# bucket.net
KiCad netlist of a schematic drawn in EAGLE
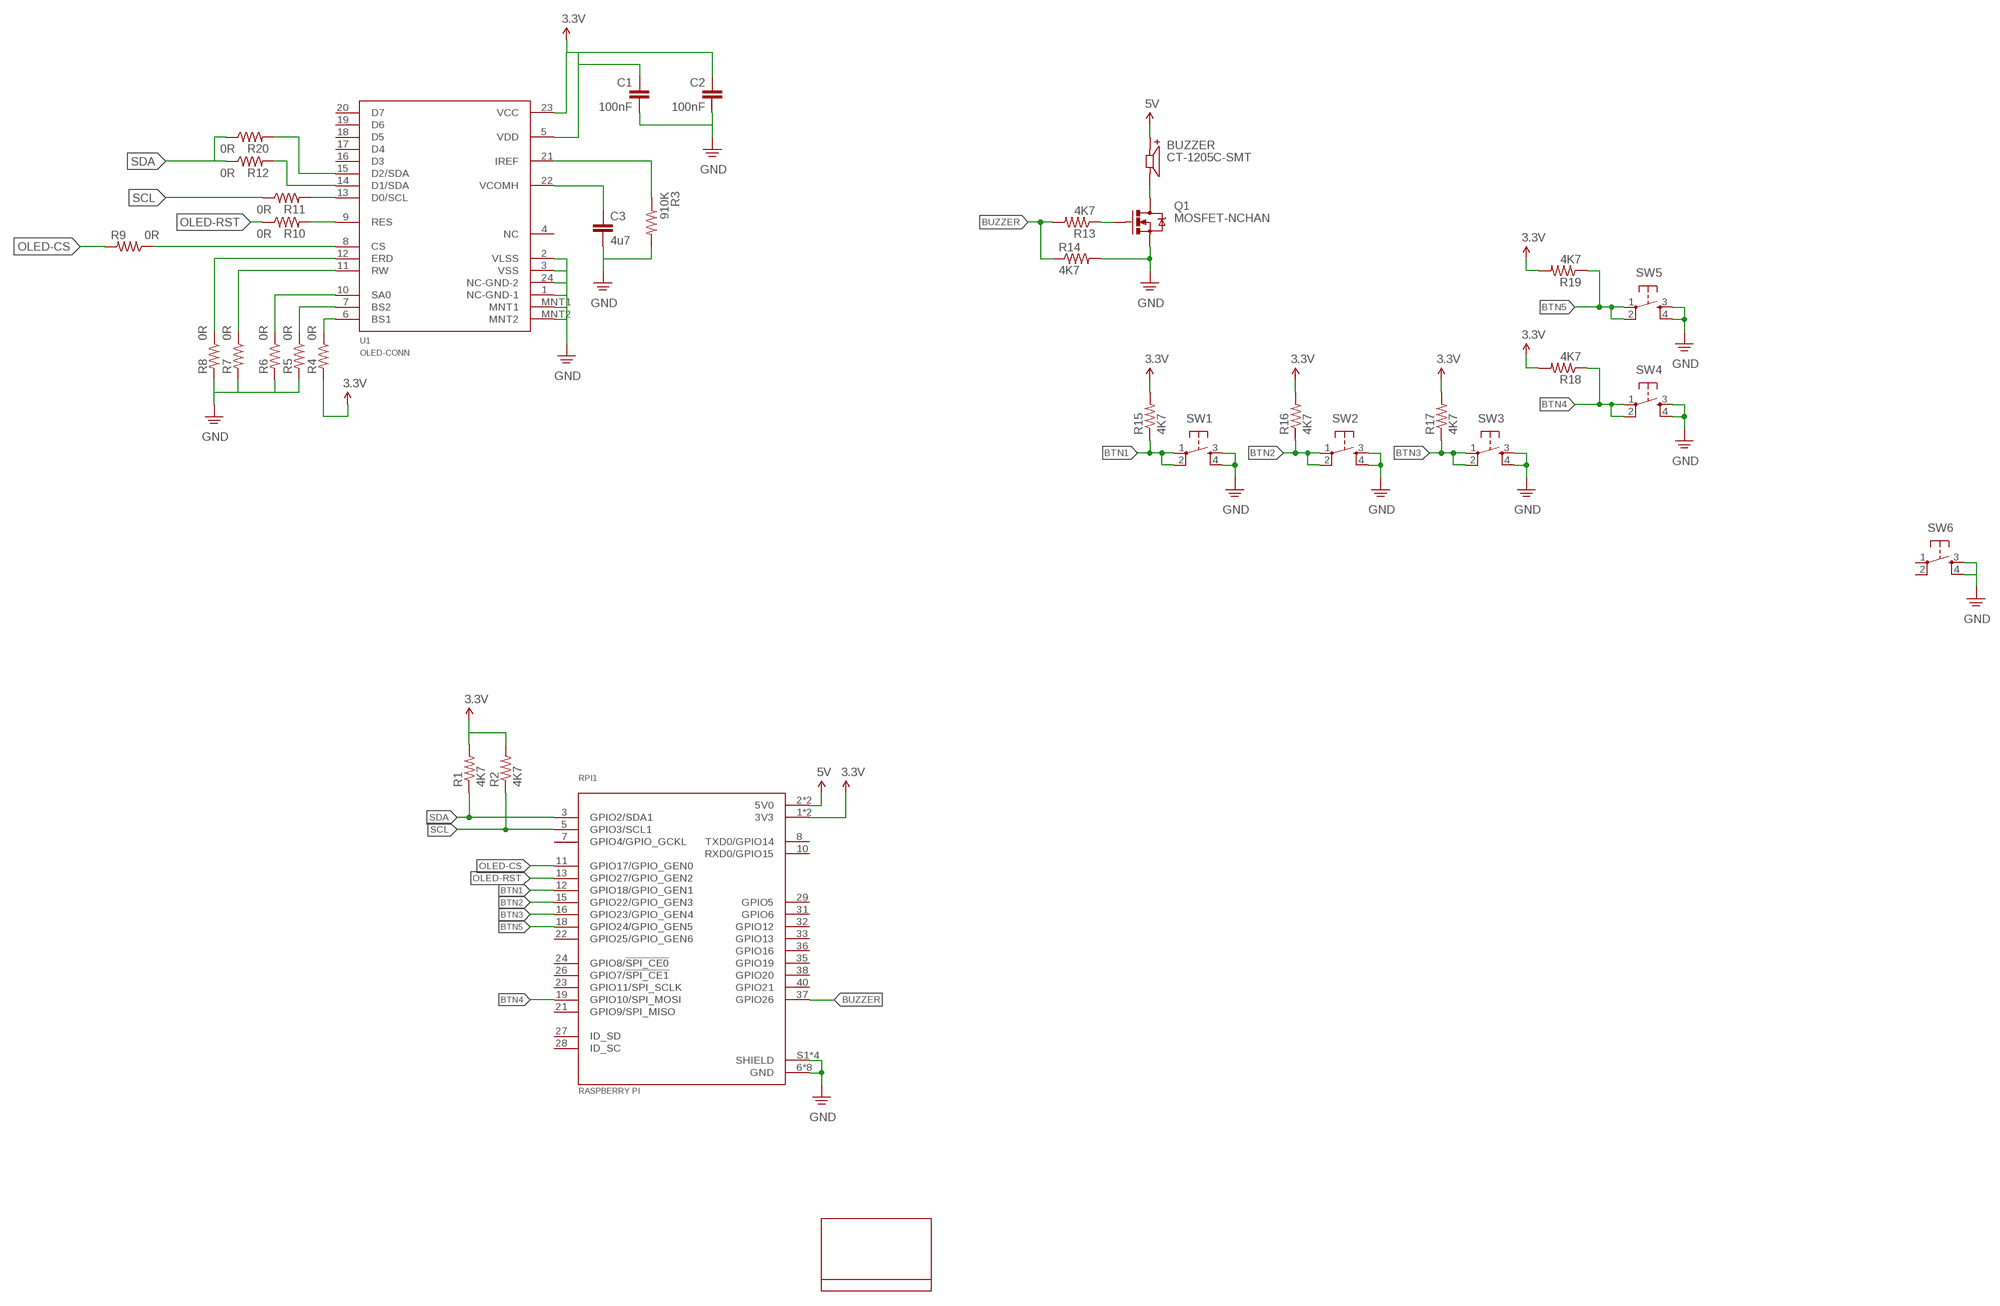
[diagram p0: schematic, sheet 1]

(export (version "E")
  (design (tool "Eeschema 10.0.6"))
  (components
    (comp (ref "BUZZER")
      (value "CT-1205C-SMT")
      (footprint "eagle-import:CUI_CT-1205C-SMT")
      (fields (field (name "MF") "CUI DEVICES"))
      (libsource (lib "eagle-import") (part "CT-1205C-SMT"))
    )
    (comp (ref "C1")
      (value "100nF")
      (footprint "eagle-import:0603-CAP")
      (libsource (lib "eagle-import") (part "CAP0603-CAP"))
    )
    (comp (ref "C2")
      (value "100nF")
      (footprint "eagle-import:0603-CAP")
      (libsource (lib "eagle-import") (part "CAP0603-CAP"))
    )
    (comp (ref "C3")
      (value "4u7")
      (footprint "eagle-import:0603-CAP")
      (libsource (lib "eagle-import") (part "CAP0603-CAP"))
    )
    (comp (ref "Q1")
      (value "MOSFET-NCHAN")
      (footprint "eagle-import:SOT23-3")
      (libsource (lib "eagle-import") (part "MOSFET-NCHANNELSMD"))
    )
    (comp (ref "R1")
      (value "4K7")
      (footprint "eagle-import:0603-RES")
      (libsource (lib "eagle-import") (part "RESISTOR0603-RES"))
    )
    (comp (ref "R2")
      (value "4K7")
      (footprint "eagle-import:0603-RES")
      (libsource (lib "eagle-import") (part "RESISTOR0603-RES"))
    )
    (comp (ref "R3")
      (value "910K")
      (footprint "eagle-import:0603-RES")
      (libsource (lib "eagle-import") (part "RESISTOR0603-RES"))
    )
    (comp (ref "R4")
      (value "0R")
      (footprint "eagle-import:0603-RES")
      (libsource (lib "eagle-import") (part "RESISTOR0603-RES"))
    )
    (comp (ref "R5")
      (value "0R")
      (footprint "eagle-import:0603-RES")
      (libsource (lib "eagle-import") (part "RESISTOR0603-RES"))
    )
    (comp (ref "R6")
      (value "0R")
      (footprint "eagle-import:0603-RES")
      (libsource (lib "eagle-import") (part "RESISTOR0603-RES"))
    )
    (comp (ref "R7")
      (value "0R")
      (footprint "eagle-import:0603-RES")
      (libsource (lib "eagle-import") (part "RESISTOR0603-RES"))
    )
    (comp (ref "R8")
      (value "0R")
      (footprint "eagle-import:0603-RES")
      (libsource (lib "eagle-import") (part "RESISTOR0603-RES"))
    )
    (comp (ref "R9")
      (value "0R")
      (footprint "eagle-import:0603-RES")
      (libsource (lib "eagle-import") (part "RESISTOR0603-RES"))
    )
    (comp (ref "R10")
      (value "0R")
      (footprint "eagle-import:0603-RES")
      (libsource (lib "eagle-import") (part "RESISTOR0603-RES"))
    )
    (comp (ref "R11")
      (value "0R")
      (footprint "eagle-import:0603-RES")
      (libsource (lib "eagle-import") (part "RESISTOR0603-RES"))
    )
    (comp (ref "R12")
      (value "0R")
      (footprint "eagle-import:0603-RES")
      (libsource (lib "eagle-import") (part "RESISTOR0603-RES"))
    )
    (comp (ref "R13")
      (value "4K7")
      (footprint "eagle-import:0603-RES")
      (libsource (lib "eagle-import") (part "RESISTOR0603-RES"))
    )
    (comp (ref "R14")
      (value "4K7")
      (footprint "eagle-import:0603-RES")
      (libsource (lib "eagle-import") (part "RESISTOR0603-RES"))
    )
    (comp (ref "R15")
      (value "4K7")
      (footprint "eagle-import:0603-RES")
      (libsource (lib "eagle-import") (part "RESISTOR0603-RES"))
    )
    (comp (ref "R16")
      (value "4K7")
      (footprint "eagle-import:0603-RES")
      (libsource (lib "eagle-import") (part "RESISTOR0603-RES"))
    )
    (comp (ref "R17")
      (value "4K7")
      (footprint "eagle-import:0603-RES")
      (libsource (lib "eagle-import") (part "RESISTOR0603-RES"))
    )
    (comp (ref "R18")
      (value "4K7")
      (footprint "eagle-import:0603-RES")
      (libsource (lib "eagle-import") (part "RESISTOR0603-RES"))
    )
    (comp (ref "R19")
      (value "4K7")
      (footprint "eagle-import:0603-RES")
      (libsource (lib "eagle-import") (part "RESISTOR0603-RES"))
    )
    (comp (ref "R20")
      (value "0R")
      (footprint "eagle-import:0603-RES")
      (libsource (lib "eagle-import") (part "RESISTOR0603-RES"))
    )
    (comp (ref "RPI1")
      (value "RASPBERRY PI")
      (footprint "eagle-import:MODULE_RASPBERRY_PI_3_MODEL_B+")
      (libsource (lib "eagle-import") (part "RASPBERRY_PI_3_MODEL_B+"))
    )
    (comp (ref "SW1")
      (value "TAC_SWITCHPTH")
      (footprint "eagle-import:TACTILE-PTH")
      (libsource (lib "eagle-import") (part "TAC_SWITCHPTH"))
    )
    (comp (ref "SW2")
      (value "TAC_SWITCHPTH")
      (footprint "eagle-import:TACTILE-PTH")
      (libsource (lib "eagle-import") (part "TAC_SWITCHPTH"))
    )
    (comp (ref "SW3")
      (value "TAC_SWITCHPTH")
      (footprint "eagle-import:TACTILE-PTH")
      (libsource (lib "eagle-import") (part "TAC_SWITCHPTH"))
    )
    (comp (ref "SW4")
      (value "TAC_SWITCHPTH")
      (footprint "eagle-import:TACTILE-PTH")
      (libsource (lib "eagle-import") (part "TAC_SWITCHPTH"))
    )
    (comp (ref "SW5")
      (value "TAC_SWITCHPTH")
      (footprint "eagle-import:TACTILE-PTH")
      (libsource (lib "eagle-import") (part "TAC_SWITCHPTH"))
    )
    (comp (ref "SW6")
      (value "TAC_SWITCHPTH")
      (footprint "eagle-import:TACTILE-PTH")
      (libsource (lib "eagle-import") (part "TAC_SWITCHPTH"))
    )
    (comp (ref "U$1")
      (value "OLED-PANEL-1.54IN")
      (footprint "eagle-import:OLED-1.54IN")
      (libsource (lib "eagle-import") (part "OLED-PANEL-1.54IN"))
    )
    (comp (ref "U1")
      (value "OLED-CONN")
      (footprint "eagle-import:CONN24_1X24_DRC_FFC_HIR")
      (libsource (lib "eagle-import") (part "OLED-CONN"))
    )
  )
  (nets
    (net (code "1") (name "3.3V") (class "Default")
      (node (ref "C1") (pin "1") (pinfunction "1_1") (pintype "passive"))
      (node (ref "C2") (pin "1") (pinfunction "1_1") (pintype "passive"))
      (node (ref "R1") (pin "2") (pinfunction "2_2") (pintype "passive"))
      (node (ref "R15") (pin "2") (pinfunction "2_2") (pintype "passive"))
      (node (ref "R16") (pin "2") (pinfunction "2_2") (pintype "passive"))
      (node (ref "R17") (pin "2") (pinfunction "2_2") (pintype "passive"))
      (node (ref "R18") (pin "2") (pinfunction "2_2") (pintype "passive"))
      (node (ref "R19") (pin "2") (pinfunction "2_2") (pintype "passive"))
      (node (ref "R2") (pin "2") (pinfunction "2_2") (pintype "passive"))
      (node (ref "R4") (pin "2") (pinfunction "2_2") (pintype "passive"))
      (node (ref "RPI1") (pin "1") (pinfunction "3V3_1") (pintype "power_in"))
      (node (ref "RPI1") (pin "17") (pinfunction "3V3_17") (pintype "power_in"))
      (node (ref "U1") (pin "23") (pinfunction "VCC_23") (pintype "input"))
      (node (ref "U1") (pin "5") (pinfunction "VDD_5") (pintype "input"))
    )
    (net (code "2") (name "5V") (class "Default")
      (node (ref "BUZZER") (pin "1") (pinfunction "1_1") (pintype "passive"))
      (node (ref "RPI1") (pin "2") (pinfunction "5V0_2") (pintype "power_in"))
      (node (ref "RPI1") (pin "4") (pinfunction "5V0_4") (pintype "power_in"))
    )
    (net (code "3") (name "BTN1") (class "Default")
      (node (ref "R15") (pin "1") (pinfunction "1_1") (pintype "passive"))
      (node (ref "RPI1") (pin "12") (pinfunction "GPIO18/GPIO_GEN1_12") (pintype "bidirectional"))
      (node (ref "SW1") (pin "1") (pinfunction "1_1") (pintype "passive"))
      (node (ref "SW1") (pin "2") (pinfunction "2_2") (pintype "passive"))
    )
    (net (code "4") (name "BTN2") (class "Default")
      (node (ref "R16") (pin "1") (pinfunction "1_1") (pintype "passive"))
      (node (ref "RPI1") (pin "15") (pinfunction "GPIO22/GPIO_GEN3_15") (pintype "bidirectional"))
      (node (ref "SW2") (pin "1") (pinfunction "1_1") (pintype "passive"))
      (node (ref "SW2") (pin "2") (pinfunction "2_2") (pintype "passive"))
    )
    (net (code "5") (name "BTN3") (class "Default")
      (node (ref "R17") (pin "1") (pinfunction "1_1") (pintype "passive"))
      (node (ref "RPI1") (pin "16") (pinfunction "GPIO23/GPIO_GEN4_16") (pintype "bidirectional"))
      (node (ref "SW3") (pin "1") (pinfunction "1_1") (pintype "passive"))
      (node (ref "SW3") (pin "2") (pinfunction "2_2") (pintype "passive"))
    )
    (net (code "6") (name "BTN4") (class "Default")
      (node (ref "R18") (pin "1") (pinfunction "1_1") (pintype "passive"))
      (node (ref "RPI1") (pin "19") (pinfunction "GPIO10/SPI_MOSI_19") (pintype "bidirectional"))
      (node (ref "SW4") (pin "1") (pinfunction "1_1") (pintype "passive"))
      (node (ref "SW4") (pin "2") (pinfunction "2_2") (pintype "passive"))
    )
    (net (code "7") (name "BTN5") (class "Default")
      (node (ref "R19") (pin "1") (pinfunction "1_1") (pintype "passive"))
      (node (ref "RPI1") (pin "18") (pinfunction "GPIO24/GPIO_GEN5_18") (pintype "bidirectional"))
      (node (ref "SW5") (pin "1") (pinfunction "1_1") (pintype "passive"))
      (node (ref "SW5") (pin "2") (pinfunction "2_2") (pintype "passive"))
    )
    (net (code "8") (name "BUZZER") (class "Default")
      (node (ref "R13") (pin "2") (pinfunction "2_2") (pintype "passive"))
      (node (ref "R14") (pin "1") (pinfunction "1_1") (pintype "passive"))
      (node (ref "RPI1") (pin "37") (pinfunction "GPIO26_37") (pintype "bidirectional"))
    )
    (net (code "9") (name "GND") (class "Default")
      (node (ref "C1") (pin "2") (pinfunction "2_2") (pintype "passive"))
      (node (ref "C2") (pin "2") (pinfunction "2_2") (pintype "passive"))
      (node (ref "C3") (pin "2") (pinfunction "2_2") (pintype "passive"))
      (node (ref "Q1") (pin "2") (pinfunction "S_2") (pintype "passive"))
      (node (ref "R14") (pin "2") (pinfunction "2_2") (pintype "passive"))
      (node (ref "R3") (pin "2") (pinfunction "2_2") (pintype "passive"))
      (node (ref "R5") (pin "2") (pinfunction "2_2") (pintype "passive"))
      (node (ref "R6") (pin "2") (pinfunction "2_2") (pintype "passive"))
      (node (ref "R7") (pin "2") (pinfunction "2_2") (pintype "passive"))
      (node (ref "R8") (pin "2") (pinfunction "2_2") (pintype "passive"))
      (node (ref "RPI1") (pin "14") (pinfunction "GND_14") (pintype "power_in"))
      (node (ref "RPI1") (pin "20") (pinfunction "GND_20") (pintype "power_in"))
      (node (ref "RPI1") (pin "25") (pinfunction "GND_25") (pintype "power_in"))
      (node (ref "RPI1") (pin "30") (pinfunction "GND_30") (pintype "power_in"))
      (node (ref "RPI1") (pin "34") (pinfunction "GND_34") (pintype "power_in"))
      (node (ref "RPI1") (pin "39") (pinfunction "GND_39") (pintype "power_in"))
      (node (ref "RPI1") (pin "6") (pinfunction "GND_6") (pintype "power_in"))
      (node (ref "RPI1") (pin "9") (pinfunction "GND_9") (pintype "power_in"))
      (node (ref "RPI1") (pin "S1") (pinfunction "SHIELD_S1") (pintype "power_in"))
      (node (ref "RPI1") (pin "S2") (pinfunction "SHIELD_S2") (pintype "power_in"))
      (node (ref "RPI1") (pin "S3") (pinfunction "SHIELD_S3") (pintype "power_in"))
      (node (ref "RPI1") (pin "S4") (pinfunction "SHIELD_S4") (pintype "power_in"))
      (node (ref "SW1") (pin "3") (pinfunction "3_3") (pintype "passive"))
      (node (ref "SW1") (pin "4") (pinfunction "4_4") (pintype "passive"))
      (node (ref "SW2") (pin "3") (pinfunction "3_3") (pintype "passive"))
      (node (ref "SW2") (pin "4") (pinfunction "4_4") (pintype "passive"))
      (node (ref "SW3") (pin "3") (pinfunction "3_3") (pintype "passive"))
      (node (ref "SW3") (pin "4") (pinfunction "4_4") (pintype "passive"))
      (node (ref "SW4") (pin "3") (pinfunction "3_3") (pintype "passive"))
      (node (ref "SW4") (pin "4") (pinfunction "4_4") (pintype "passive"))
      (node (ref "SW5") (pin "3") (pinfunction "3_3") (pintype "passive"))
      (node (ref "SW5") (pin "4") (pinfunction "4_4") (pintype "passive"))
      (node (ref "SW6") (pin "3") (pinfunction "3_3") (pintype "passive"))
      (node (ref "SW6") (pin "4") (pinfunction "4_4") (pintype "passive"))
      (node (ref "U1") (pin "1") (pinfunction "NC-GND-1_1") (pintype "input"))
      (node (ref "U1") (pin "2") (pinfunction "VLSS_2") (pintype "input"))
      (node (ref "U1") (pin "24") (pinfunction "NC-GND-2_24") (pintype "input"))
      (node (ref "U1") (pin "3") (pinfunction "VSS_3") (pintype "input"))
      (node (ref "U1") (pin "MNT1") (pinfunction "MNT1_MNT1") (pintype "input"))
      (node (ref "U1") (pin "MNT2") (pinfunction "MNT2_MNT2") (pintype "input"))
    )
    (net (code "10") (name "Net-(Q1-D)") (class "Default")
      (node (ref "BUZZER") (pin "2") (pinfunction "2_2") (pintype "passive"))
      (node (ref "Q1") (pin "3") (pinfunction "D_3") (pintype "passive"))
    )
    (net (code "11") (name "Net-(Q1-G)") (class "Default")
      (node (ref "Q1") (pin "1") (pinfunction "G_1") (pintype "passive"))
      (node (ref "R13") (pin "1") (pinfunction "1_1") (pintype "passive"))
    )
    (net (code "12") (name "Net-(U1-BS1)") (class "Default")
      (node (ref "R4") (pin "1") (pinfunction "1_1") (pintype "passive"))
      (node (ref "U1") (pin "6") (pinfunction "BS1_6") (pintype "input"))
    )
    (net (code "13") (name "Net-(U1-BS2)") (class "Default")
      (node (ref "R5") (pin "1") (pinfunction "1_1") (pintype "passive"))
      (node (ref "U1") (pin "7") (pinfunction "BS2_7") (pintype "input"))
    )
    (net (code "14") (name "Net-(U1-CS)") (class "Default")
      (node (ref "R9") (pin "1") (pinfunction "1_1") (pintype "passive"))
      (node (ref "U1") (pin "8") (pinfunction "CS_8") (pintype "input"))
    )
    (net (code "15") (name "Net-(U1-D0{slash}SCL)") (class "Default")
      (node (ref "R11") (pin "2") (pinfunction "2_2") (pintype "passive"))
      (node (ref "U1") (pin "13") (pinfunction "D0/SCL_13") (pintype "input"))
    )
    (net (code "16") (name "Net-(U1-D1{slash}SDA)") (class "Default")
      (node (ref "R12") (pin "2") (pinfunction "2_2") (pintype "passive"))
      (node (ref "U1") (pin "14") (pinfunction "D1/SDA_14") (pintype "input"))
    )
    (net (code "17") (name "Net-(U1-D2{slash}SDA)") (class "Default")
      (node (ref "R20") (pin "2") (pinfunction "2_2") (pintype "passive"))
      (node (ref "U1") (pin "15") (pinfunction "D2/SDA_15") (pintype "input"))
    )
    (net (code "18") (name "Net-(U1-ERD)") (class "Default")
      (node (ref "R8") (pin "1") (pinfunction "1_1") (pintype "passive"))
      (node (ref "U1") (pin "12") (pinfunction "ERD_12") (pintype "input"))
    )
    (net (code "19") (name "Net-(U1-IREF)") (class "Default")
      (node (ref "R3") (pin "1") (pinfunction "1_1") (pintype "passive"))
      (node (ref "U1") (pin "21") (pinfunction "IREF_21") (pintype "input"))
    )
    (net (code "20") (name "Net-(U1-RES)") (class "Default")
      (node (ref "R10") (pin "2") (pinfunction "2_2") (pintype "passive"))
      (node (ref "U1") (pin "9") (pinfunction "RES_9") (pintype "input"))
    )
    (net (code "21") (name "Net-(U1-RW)") (class "Default")
      (node (ref "R7") (pin "1") (pinfunction "1_1") (pintype "passive"))
      (node (ref "U1") (pin "11") (pinfunction "RW_11") (pintype "input"))
    )
    (net (code "22") (name "Net-(U1-SA0)") (class "Default")
      (node (ref "R6") (pin "1") (pinfunction "1_1") (pintype "passive"))
      (node (ref "U1") (pin "10") (pinfunction "SA0_10") (pintype "input"))
    )
    (net (code "23") (name "Net-(U1-VCOMH)") (class "Default")
      (node (ref "C3") (pin "1") (pinfunction "1_1") (pintype "passive"))
      (node (ref "U1") (pin "22") (pinfunction "VCOMH_22") (pintype "input"))
    )
    (net (code "24") (name "OLED-CS") (class "Default")
      (node (ref "R9") (pin "2") (pinfunction "2_2") (pintype "passive"))
      (node (ref "RPI1") (pin "11") (pinfunction "GPIO17/GPIO_GEN0_11") (pintype "bidirectional"))
    )
    (net (code "25") (name "OLED-RST") (class "Default")
      (node (ref "R10") (pin "1") (pinfunction "1_1") (pintype "passive"))
      (node (ref "RPI1") (pin "13") (pinfunction "GPIO27/GPIO_GEN2_13") (pintype "bidirectional"))
    )
    (net (code "26") (name "SCL") (class "Default")
      (node (ref "R11") (pin "1") (pinfunction "1_1") (pintype "passive"))
      (node (ref "R2") (pin "1") (pinfunction "1_1") (pintype "passive"))
      (node (ref "RPI1") (pin "5") (pinfunction "GPIO3/SCL1_5") (pintype "bidirectional"))
    )
    (net (code "27") (name "SDA") (class "Default")
      (node (ref "R1") (pin "1") (pinfunction "1_1") (pintype "passive"))
      (node (ref "R12") (pin "1") (pinfunction "1_1") (pintype "passive"))
      (node (ref "R20") (pin "1") (pinfunction "1_1") (pintype "passive"))
      (node (ref "RPI1") (pin "3") (pinfunction "GPIO2/SDA1_3") (pintype "bidirectional"))
    )
    (net (code "28") (name "unconnected-(RPI1-GPIO4{slash}GPIO_GCKL-Pad7)") (class "Default")
      (node (ref "RPI1") (pin "7") (pinfunction "GPIO4/GPIO_GCKL_7") (pintype "bidirectional"))
    )
    (net (code "29") (name "unconnected-(RPI1-GPIO5-Pad29)") (class "Default")
      (node (ref "RPI1") (pin "29") (pinfunction "GPIO5_29") (pintype "bidirectional"))
    )
    (net (code "30") (name "unconnected-(RPI1-GPIO6-Pad31)") (class "Default")
      (node (ref "RPI1") (pin "31") (pinfunction "GPIO6_31") (pintype "bidirectional"))
    )
    (net (code "31") (name "unconnected-(RPI1-GPIO7{slash}~{SPI_CE1}-Pad26)") (class "Default")
      (node (ref "RPI1") (pin "26") (pinfunction "GPIO7/~{SPI_CE1}_26") (pintype "bidirectional"))
    )
    (net (code "32") (name "unconnected-(RPI1-GPIO8{slash}~{SPI_CE0}-Pad24)") (class "Default")
      (node (ref "RPI1") (pin "24") (pinfunction "GPIO8/~{SPI_CE0}_24") (pintype "bidirectional"))
    )
    (net (code "33") (name "unconnected-(RPI1-GPIO9{slash}SPI_MISO-Pad21)") (class "Default")
      (node (ref "RPI1") (pin "21") (pinfunction "GPIO9/SPI_MISO_21") (pintype "bidirectional"))
    )
    (net (code "34") (name "unconnected-(RPI1-GPIO11{slash}SPI_SCLK-Pad23)") (class "Default")
      (node (ref "RPI1") (pin "23") (pinfunction "GPIO11/SPI_SCLK_23") (pintype "bidirectional"))
    )
    (net (code "35") (name "unconnected-(RPI1-GPIO12-Pad32)") (class "Default")
      (node (ref "RPI1") (pin "32") (pinfunction "GPIO12_32") (pintype "bidirectional"))
    )
    (net (code "36") (name "unconnected-(RPI1-GPIO13-Pad33)") (class "Default")
      (node (ref "RPI1") (pin "33") (pinfunction "GPIO13_33") (pintype "bidirectional"))
    )
    (net (code "37") (name "unconnected-(RPI1-GPIO16-Pad36)") (class "Default")
      (node (ref "RPI1") (pin "36") (pinfunction "GPIO16_36") (pintype "bidirectional"))
    )
    (net (code "38") (name "unconnected-(RPI1-GPIO19-Pad35)") (class "Default")
      (node (ref "RPI1") (pin "35") (pinfunction "GPIO19_35") (pintype "bidirectional"))
    )
    (net (code "39") (name "unconnected-(RPI1-GPIO20-Pad38)") (class "Default")
      (node (ref "RPI1") (pin "38") (pinfunction "GPIO20_38") (pintype "bidirectional"))
    )
    (net (code "40") (name "unconnected-(RPI1-GPIO21-Pad40)") (class "Default")
      (node (ref "RPI1") (pin "40") (pinfunction "GPIO21_40") (pintype "bidirectional"))
    )
    (net (code "41") (name "unconnected-(RPI1-GPIO25{slash}GPIO_GEN6-Pad22)") (class "Default")
      (node (ref "RPI1") (pin "22") (pinfunction "GPIO25/GPIO_GEN6_22") (pintype "bidirectional"))
    )
    (net (code "42") (name "unconnected-(RPI1-ID_SC-Pad28)") (class "Default")
      (node (ref "RPI1") (pin "28") (pinfunction "ID_SC_28") (pintype "bidirectional"))
    )
    (net (code "43") (name "unconnected-(RPI1-ID_SD-Pad27)") (class "Default")
      (node (ref "RPI1") (pin "27") (pinfunction "ID_SD_27") (pintype "bidirectional"))
    )
    (net (code "44") (name "unconnected-(RPI1-RXD0{slash}GPIO15-Pad10)") (class "Default")
      (node (ref "RPI1") (pin "10") (pinfunction "RXD0/GPIO15_10") (pintype "bidirectional"))
    )
    (net (code "45") (name "unconnected-(RPI1-TXD0{slash}GPIO14-Pad8)") (class "Default")
      (node (ref "RPI1") (pin "8") (pinfunction "TXD0/GPIO14_8") (pintype "bidirectional"))
    )
    (net (code "46") (name "unconnected-(SW6-Pad1)") (class "Default")
      (node (ref "SW6") (pin "1") (pinfunction "1_1") (pintype "passive"))
    )
    (net (code "47") (name "unconnected-(SW6-Pad2)") (class "Default")
      (node (ref "SW6") (pin "2") (pinfunction "2_2") (pintype "passive"))
    )
    (net (code "48") (name "unconnected-(U1-D3-Pad16)") (class "Default")
      (node (ref "U1") (pin "16") (pinfunction "D3_16") (pintype "input"))
    )
    (net (code "49") (name "unconnected-(U1-D4-Pad17)") (class "Default")
      (node (ref "U1") (pin "17") (pinfunction "D4_17") (pintype "input"))
    )
    (net (code "50") (name "unconnected-(U1-D5-Pad18)") (class "Default")
      (node (ref "U1") (pin "18") (pinfunction "D5_18") (pintype "input"))
    )
    (net (code "51") (name "unconnected-(U1-D6-Pad19)") (class "Default")
      (node (ref "U1") (pin "19") (pinfunction "D6_19") (pintype "input"))
    )
    (net (code "52") (name "unconnected-(U1-D7-Pad20)") (class "Default")
      (node (ref "U1") (pin "20") (pinfunction "D7_20") (pintype "input"))
    )
    (net (code "53") (name "unconnected-(U1-NC-Pad4)") (class "Default")
      (node (ref "U1") (pin "4") (pinfunction "NC_4") (pintype "input"))
    )
  )
)
